# Dot_matrix_V1_1.net
KiCad netlist of a schematic drawn in Altium Designer
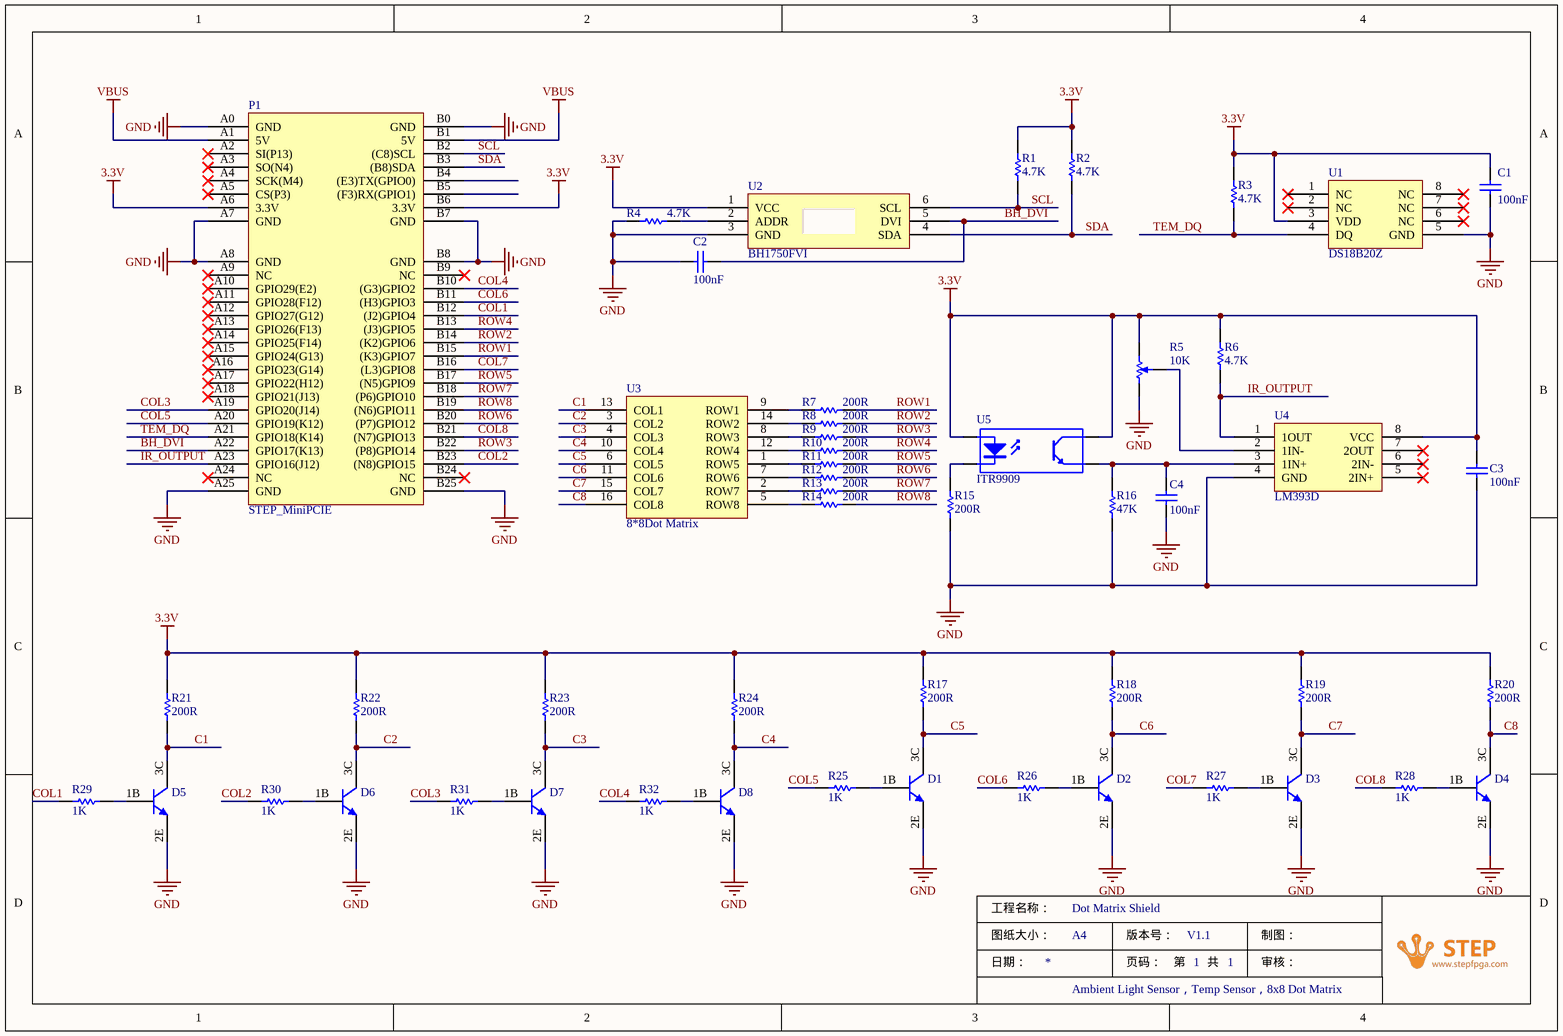
[diagram p0: Dot_matrix_V1.1.SchDoc]

(export (version "E")
  (design (tool "Eeschema 10.0.6"))
  (components
    (comp (ref "C1")
      (value "100nF")
      (footprint "CAP0603")
      (description "Capacitor")
      (libsource (lib "Ze_Zhang") (part "Cap"))
    )
    (comp (ref "C2")
      (value "100nF")
      (footprint "CAP0603")
      (description "Capacitor")
      (libsource (lib "Ze_Zhang") (part "Cap"))
    )
    (comp (ref "C3")
      (value "100nF")
      (footprint "CAP0603")
      (description "Capacitor")
      (libsource (lib "Ze_Zhang") (part "Cap"))
    )
    (comp (ref "C4")
      (value "100nF")
      (footprint "CAP0603")
      (description "Capacitor")
      (libsource (lib "Ze_Zhang") (part "Cap"))
    )
    (comp (ref "D1")
      (value "s9013")
      (footprint "SOT-23 s9013")
      (description "NPN三极管")
      (libsource (lib "Ze_Zhang") (part "s9013"))
    )
    (comp (ref "D2")
      (value "s9013")
      (footprint "SOT-23 s9013")
      (description "NPN三极管")
      (libsource (lib "Ze_Zhang") (part "s9013"))
    )
    (comp (ref "D3")
      (value "s9013")
      (footprint "SOT-23 s9013")
      (description "NPN三极管")
      (libsource (lib "Ze_Zhang") (part "s9013"))
    )
    (comp (ref "D4")
      (value "s9013")
      (footprint "SOT-23 s9013")
      (description "NPN三极管")
      (libsource (lib "Ze_Zhang") (part "s9013"))
    )
    (comp (ref "D5")
      (value "s9013")
      (footprint "SOT-23 s9013")
      (description "NPN三极管")
      (libsource (lib "Ze_Zhang") (part "s9013"))
    )
    (comp (ref "D6")
      (value "s9013")
      (footprint "SOT-23 s9013")
      (description "NPN三极管")
      (libsource (lib "Ze_Zhang") (part "s9013"))
    )
    (comp (ref "D7")
      (value "s9013")
      (footprint "SOT-23 s9013")
      (description "NPN三极管")
      (libsource (lib "Ze_Zhang") (part "s9013"))
    )
    (comp (ref "D8")
      (value "s9013")
      (footprint "SOT-23 s9013")
      (description "NPN三极管")
      (libsource (lib "Ze_Zhang") (part "s9013"))
    )
    (comp (ref "P1")
      (value "STEP_MiniPCIE")
      (footprint "STEP_miniPCI-E")
      (description "8mm MiniPCIE interface")
      (libsource (lib "Ze_Zhang") (part "STEP_MiniPCIE"))
    )
    (comp (ref "R1") (value "4.7K") (footprint "RES0603") (libsource (lib "Ze_Zhang") (part "Res")))
    (comp (ref "R2") (value "4.7K") (footprint "RES0603") (libsource (lib "Ze_Zhang") (part "Res")))
    (comp (ref "R3") (value "4.7K") (footprint "RES0603") (libsource (lib "Ze_Zhang") (part "Res")))
    (comp (ref "R4") (value "4.7K") (footprint "RES0603") (libsource (lib "Ze_Zhang") (part "Res")))
    (comp (ref "R5")
      (value "10K")
      (footprint "POT3MM")
      (description "可调电阻3mm*3mm")
      (fields (field (name "PARTNUMBER") "EXM3GSX50B14") (field (name "MANUFACTURER") "Panasonic"))
      (libsource (lib "Ze_Zhang") (part "Square Trimming Potentiometer"))
    )
    (comp (ref "R6") (value "4.7K") (footprint "RES0603") (libsource (lib "Ze_Zhang") (part "Res")))
    (comp (ref "R7") (value "200R") (footprint "RES0603") (libsource (lib "Ze_Zhang") (part "Res")))
    (comp (ref "R8") (value "200R") (footprint "RES0603") (libsource (lib "Ze_Zhang") (part "Res")))
    (comp (ref "R9") (value "200R") (footprint "RES0603") (libsource (lib "Ze_Zhang") (part "Res")))
    (comp (ref "R10") (value "200R") (footprint "RES0603") (libsource (lib "Ze_Zhang") (part "Res")))
    (comp (ref "R11") (value "200R") (footprint "RES0603") (libsource (lib "Ze_Zhang") (part "Res")))
    (comp (ref "R12") (value "200R") (footprint "RES0603") (libsource (lib "Ze_Zhang") (part "Res")))
    (comp (ref "R13") (value "200R") (footprint "RES0603") (libsource (lib "Ze_Zhang") (part "Res")))
    (comp (ref "R14") (value "200R") (footprint "RES0603") (libsource (lib "Ze_Zhang") (part "Res")))
    (comp (ref "R15") (value "200R") (footprint "RES0603") (libsource (lib "Ze_Zhang") (part "Res")))
    (comp (ref "R16") (value "47K") (footprint "RES0603") (libsource (lib "Ze_Zhang") (part "Res")))
    (comp (ref "R17") (value "200R") (footprint "RES0603") (libsource (lib "Ze_Zhang") (part "Res")))
    (comp (ref "R18") (value "200R") (footprint "RES0603") (libsource (lib "Ze_Zhang") (part "Res")))
    (comp (ref "R19") (value "200R") (footprint "RES0603") (libsource (lib "Ze_Zhang") (part "Res")))
    (comp (ref "R20") (value "200R") (footprint "RES0603") (libsource (lib "Ze_Zhang") (part "Res")))
    (comp (ref "R21") (value "200R") (footprint "RES0603") (libsource (lib "Ze_Zhang") (part "Res")))
    (comp (ref "R22") (value "200R") (footprint "RES0603") (libsource (lib "Ze_Zhang") (part "Res")))
    (comp (ref "R23") (value "200R") (footprint "RES0603") (libsource (lib "Ze_Zhang") (part "Res")))
    (comp (ref "R24") (value "200R") (footprint "RES0603") (libsource (lib "Ze_Zhang") (part "Res")))
    (comp (ref "R25") (value "1K") (footprint "RES0603") (libsource (lib "Ze_Zhang") (part "Res")))
    (comp (ref "R26") (value "1K") (footprint "RES0603") (libsource (lib "Ze_Zhang") (part "Res")))
    (comp (ref "R27") (value "1K") (footprint "RES0603") (libsource (lib "Ze_Zhang") (part "Res")))
    (comp (ref "R28") (value "1K") (footprint "RES0603") (libsource (lib "Ze_Zhang") (part "Res")))
    (comp (ref "R29") (value "1K") (footprint "RES0603") (libsource (lib "Ze_Zhang") (part "Res")))
    (comp (ref "R30") (value "1K") (footprint "RES0603") (libsource (lib "Ze_Zhang") (part "Res")))
    (comp (ref "R31") (value "1K") (footprint "RES0603") (libsource (lib "Ze_Zhang") (part "Res")))
    (comp (ref "R32") (value "1K") (footprint "RES0603") (libsource (lib "Ze_Zhang") (part "Res")))
    (comp (ref "U1")
      (value "DS18B20Z")
      (footprint "SOP8")
      (description "温度传感器DS18B20,单总线，SOP8封装")
      (fields (field (name "MANUFACTURER") "Dallas"))
      (libsource (lib "Ze_Zhang") (part "DS18B20Z"))
    )
    (comp (ref "U2")
      (value "BH1750FVI")
      (footprint "WSOF6I")
      (description "I2C接口环境光传感器")
      (fields (field (name "MANUFACTURER") "RHOM"))
      (libsource (lib "Ze_Zhang") (part "BH1750FVI"))
    )
    (comp (ref "U3")
      (value "8*8Dot Matrix")
      (footprint "8*8Dot Matrix")
      (description "8*8LED点阵，尺寸为32mm*32mm , 共阴")
      (fields (field (name "PARTNUMBER") "1088AS"))
      (libsource (lib "Ze_Zhang") (part "8*8Dot Matrix"))
    )
    (comp (ref "U4")
      (value "LM393D")
      (footprint "SOP8")
      (description "双路电压比较器")
      (fields (field (name "MANUFACTURER") "Texas Instruments"))
      (libsource (lib "Ze_Zhang") (part "LM393D"))
    )
    (comp (ref "U5")
      (value "ITR9909")
      (footprint "ITR9909")
      (description "红外对管，4pins")
      (fields (field (name "MANUFACTURER") "EVERLIGHT  ELECTRONICS"))
      (libsource (lib "Ze_Zhang") (part "ITR9909"))
    )
  )
  (nets
    (net (code "1") (name "/BH_DVI") (class "Default")
      (node (ref "C2") (pin "1") (pinfunction "1_1") (pintype "passive"))
      (node (ref "P1") (pin "A22") (pinfunction "GPIO17(K13)_A22") (pintype "passive"))
      (node (ref "U2") (pin "5") (pinfunction "DVI_5") (pintype "passive"))
    )
    (net (code "2") (name "/C1") (class "Default")
      (node (ref "D5") (pin "3C") (pinfunction "3C_3C") (pintype "passive"))
      (node (ref "R21") (pin "1") (pinfunction "1_1") (pintype "passive"))
      (node (ref "U3") (pin "13") (pinfunction "COL1_13") (pintype "passive"))
    )
    (net (code "3") (name "/C2") (class "Default")
      (node (ref "D6") (pin "3C") (pinfunction "3C_3C") (pintype "passive"))
      (node (ref "R22") (pin "1") (pinfunction "1_1") (pintype "passive"))
      (node (ref "U3") (pin "3") (pinfunction "COL2_3") (pintype "passive"))
    )
    (net (code "4") (name "/C3") (class "Default")
      (node (ref "D7") (pin "3C") (pinfunction "3C_3C") (pintype "passive"))
      (node (ref "R23") (pin "1") (pinfunction "1_1") (pintype "passive"))
      (node (ref "U3") (pin "4") (pinfunction "COL3_4") (pintype "passive"))
    )
    (net (code "5") (name "/C4") (class "Default")
      (node (ref "D8") (pin "3C") (pinfunction "3C_3C") (pintype "passive"))
      (node (ref "R24") (pin "1") (pinfunction "1_1") (pintype "passive"))
      (node (ref "U3") (pin "10") (pinfunction "COL4_10") (pintype "passive"))
    )
    (net (code "6") (name "/C5") (class "Default")
      (node (ref "D1") (pin "3C") (pinfunction "3C_3C") (pintype "passive"))
      (node (ref "R17") (pin "1") (pinfunction "1_1") (pintype "passive"))
      (node (ref "U3") (pin "6") (pinfunction "COL5_6") (pintype "passive"))
    )
    (net (code "7") (name "/C6") (class "Default")
      (node (ref "D2") (pin "3C") (pinfunction "3C_3C") (pintype "passive"))
      (node (ref "R18") (pin "1") (pinfunction "1_1") (pintype "passive"))
      (node (ref "U3") (pin "11") (pinfunction "COL6_11") (pintype "passive"))
    )
    (net (code "8") (name "/C7") (class "Default")
      (node (ref "D3") (pin "3C") (pinfunction "3C_3C") (pintype "passive"))
      (node (ref "R19") (pin "1") (pinfunction "1_1") (pintype "passive"))
      (node (ref "U3") (pin "15") (pinfunction "COL7_15") (pintype "passive"))
    )
    (net (code "9") (name "/C8") (class "Default")
      (node (ref "D4") (pin "3C") (pinfunction "3C_3C") (pintype "passive"))
      (node (ref "R20") (pin "1") (pinfunction "1_1") (pintype "passive"))
      (node (ref "U3") (pin "16") (pinfunction "COL8_16") (pintype "passive"))
    )
    (net (code "10") (name "/COL1") (class "Default")
      (node (ref "P1") (pin "B12") (pinfunction "(J2)GPIO4_B12") (pintype "passive"))
      (node (ref "R29") (pin "1") (pinfunction "1_1") (pintype "passive"))
    )
    (net (code "11") (name "/COL2") (class "Default")
      (node (ref "P1") (pin "B23") (pinfunction "(N8)GPIO15_B23") (pintype "passive"))
      (node (ref "R30") (pin "1") (pinfunction "1_1") (pintype "passive"))
    )
    (net (code "12") (name "/COL3") (class "Default")
      (node (ref "P1") (pin "A19") (pinfunction "GPIO20(J14)_A19") (pintype "passive"))
      (node (ref "R31") (pin "1") (pinfunction "1_1") (pintype "passive"))
    )
    (net (code "13") (name "/COL4") (class "Default")
      (node (ref "P1") (pin "B10") (pinfunction "(G3)GPIO2_B10") (pintype "passive"))
      (node (ref "R32") (pin "1") (pinfunction "1_1") (pintype "passive"))
    )
    (net (code "14") (name "/COL5") (class "Default")
      (node (ref "P1") (pin "A20") (pinfunction "GPIO19(K12)_A20") (pintype "passive"))
      (node (ref "R25") (pin "1") (pinfunction "1_1") (pintype "passive"))
    )
    (net (code "15") (name "/COL6") (class "Default")
      (node (ref "P1") (pin "B11") (pinfunction "(H3)GPIO3_B11") (pintype "passive"))
      (node (ref "R26") (pin "1") (pinfunction "1_1") (pintype "passive"))
    )
    (net (code "16") (name "/COL7") (class "Default")
      (node (ref "P1") (pin "B16") (pinfunction "(L3)GPIO8_B16") (pintype "passive"))
      (node (ref "R27") (pin "1") (pinfunction "1_1") (pintype "passive"))
    )
    (net (code "17") (name "/COL8") (class "Default")
      (node (ref "P1") (pin "B21") (pinfunction "(N7)GPIO13_B21") (pintype "passive"))
      (node (ref "R28") (pin "1") (pinfunction "1_1") (pintype "passive"))
    )
    (net (code "18") (name "/IR_OUTPUT") (class "Default")
      (node (ref "P1") (pin "A23") (pinfunction "GPIO16(J12)_A23") (pintype "passive"))
      (node (ref "R6") (pin "1") (pinfunction "1_1") (pintype "passive"))
      (node (ref "U4") (pin "1") (pinfunction "1OUT_1") (pintype "passive"))
    )
    (net (code "19") (name "/ROW1") (class "Default")
      (node (ref "P1") (pin "B15") (pinfunction "(K3)GPIO7_B15") (pintype "passive"))
      (node (ref "R7") (pin "2") (pinfunction "2_2") (pintype "passive"))
    )
    (net (code "20") (name "/ROW2") (class "Default")
      (node (ref "P1") (pin "B14") (pinfunction "(K2)GPIO6_B14") (pintype "passive"))
      (node (ref "R8") (pin "2") (pinfunction "2_2") (pintype "passive"))
    )
    (net (code "21") (name "/ROW3") (class "Default")
      (node (ref "P1") (pin "B22") (pinfunction "(P8)GPIO14_B22") (pintype "passive"))
      (node (ref "R9") (pin "2") (pinfunction "2_2") (pintype "passive"))
    )
    (net (code "22") (name "/ROW4") (class "Default")
      (node (ref "P1") (pin "B13") (pinfunction "(J3)GPIO5_B13") (pintype "passive"))
      (node (ref "R10") (pin "2") (pinfunction "2_2") (pintype "passive"))
    )
    (net (code "23") (name "/ROW5") (class "Default")
      (node (ref "P1") (pin "B17") (pinfunction "(N5)GPIO9_B17") (pintype "passive"))
      (node (ref "R11") (pin "2") (pinfunction "2_2") (pintype "passive"))
    )
    (net (code "24") (name "/ROW6") (class "Default")
      (node (ref "P1") (pin "B20") (pinfunction "(P7)GPIO12_B20") (pintype "passive"))
      (node (ref "R12") (pin "2") (pinfunction "2_2") (pintype "passive"))
    )
    (net (code "25") (name "/ROW7") (class "Default")
      (node (ref "P1") (pin "B18") (pinfunction "(P6)GPIO10_B18") (pintype "passive"))
      (node (ref "R13") (pin "2") (pinfunction "2_2") (pintype "passive"))
    )
    (net (code "26") (name "/ROW8") (class "Default")
      (node (ref "P1") (pin "B19") (pinfunction "(N6)GPIO11_B19") (pintype "passive"))
      (node (ref "R14") (pin "2") (pinfunction "2_2") (pintype "passive"))
    )
    (net (code "27") (name "/SCL") (class "Default")
      (node (ref "P1") (pin "B2") (pinfunction "(C8)SCL_B2") (pintype "passive"))
      (node (ref "R1") (pin "1") (pinfunction "1_1") (pintype "passive"))
      (node (ref "U2") (pin "6") (pinfunction "SCL_6") (pintype "passive"))
    )
    (net (code "28") (name "/SDA") (class "Default")
      (node (ref "P1") (pin "B3") (pinfunction "(B8)SDA_B3") (pintype "passive"))
      (node (ref "R2") (pin "1") (pinfunction "1_1") (pintype "passive"))
      (node (ref "U2") (pin "4") (pinfunction "SDA_4") (pintype "passive"))
    )
    (net (code "29") (name "/TEM_DQ") (class "Default")
      (node (ref "P1") (pin "A21") (pinfunction "GPIO18(K14)_A21") (pintype "passive"))
      (node (ref "R3") (pin "1") (pinfunction "1_1") (pintype "passive"))
      (node (ref "U1") (pin "4") (pinfunction "DQ_4") (pintype "passive"))
    )
    (net (code "30") (name "3.3V") (class "Default")
      (node (ref "C1") (pin "2") (pinfunction "2_2") (pintype "passive"))
      (node (ref "C3") (pin "2") (pinfunction "2_2") (pintype "passive"))
      (node (ref "P1") (pin "A6") (pinfunction "3.3V_A6") (pintype "passive"))
      (node (ref "P1") (pin "B6") (pinfunction "3.3V_B6") (pintype "passive"))
      (node (ref "R1") (pin "2") (pinfunction "2_2") (pintype "passive"))
      (node (ref "R17") (pin "2") (pinfunction "2_2") (pintype "passive"))
      (node (ref "R18") (pin "2") (pinfunction "2_2") (pintype "passive"))
      (node (ref "R19") (pin "2") (pinfunction "2_2") (pintype "passive"))
      (node (ref "R2") (pin "2") (pinfunction "2_2") (pintype "passive"))
      (node (ref "R20") (pin "2") (pinfunction "2_2") (pintype "passive"))
      (node (ref "R21") (pin "2") (pinfunction "2_2") (pintype "passive"))
      (node (ref "R22") (pin "2") (pinfunction "2_2") (pintype "passive"))
      (node (ref "R23") (pin "2") (pinfunction "2_2") (pintype "passive"))
      (node (ref "R24") (pin "2") (pinfunction "2_2") (pintype "passive"))
      (node (ref "R3") (pin "2") (pinfunction "2_2") (pintype "passive"))
      (node (ref "R5") (pin "CW") (pinfunction "+_CW") (pintype "passive"))
      (node (ref "R6") (pin "2") (pinfunction "2_2") (pintype "passive"))
      (node (ref "U1") (pin "3") (pinfunction "VDD_3") (pintype "passive"))
      (node (ref "U2") (pin "1") (pinfunction "VCC_1") (pintype "passive"))
      (node (ref "U4") (pin "8") (pinfunction "VCC_8") (pintype "passive"))
      (node (ref "U5") (pin "2") (pinfunction "2_2") (pintype "passive"))
      (node (ref "U5") (pin "4") (pinfunction "4_4") (pintype "passive"))
    )
    (net (code "31") (name "GND") (class "Default")
      (node (ref "C1") (pin "1") (pinfunction "1_1") (pintype "passive"))
      (node (ref "C2") (pin "2") (pinfunction "2_2") (pintype "passive"))
      (node (ref "C3") (pin "1") (pinfunction "1_1") (pintype "passive"))
      (node (ref "C4") (pin "1") (pinfunction "1_1") (pintype "passive"))
      (node (ref "D1") (pin "2E") (pinfunction "2E_2E") (pintype "passive"))
      (node (ref "D2") (pin "2E") (pinfunction "2E_2E") (pintype "passive"))
      (node (ref "D3") (pin "2E") (pinfunction "2E_2E") (pintype "passive"))
      (node (ref "D4") (pin "2E") (pinfunction "2E_2E") (pintype "passive"))
      (node (ref "D5") (pin "2E") (pinfunction "2E_2E") (pintype "passive"))
      (node (ref "D6") (pin "2E") (pinfunction "2E_2E") (pintype "passive"))
      (node (ref "D7") (pin "2E") (pinfunction "2E_2E") (pintype "passive"))
      (node (ref "D8") (pin "2E") (pinfunction "2E_2E") (pintype "passive"))
      (node (ref "P1") (pin "A0") (pinfunction "GND_A0") (pintype "passive"))
      (node (ref "P1") (pin "A25") (pinfunction "GND_A25") (pintype "passive"))
      (node (ref "P1") (pin "A7") (pinfunction "GND_A7") (pintype "passive"))
      (node (ref "P1") (pin "A8") (pinfunction "GND_A8") (pintype "passive"))
      (node (ref "P1") (pin "B0") (pinfunction "GND_B0") (pintype "passive"))
      (node (ref "P1") (pin "B25") (pinfunction "GND_B25") (pintype "passive"))
      (node (ref "P1") (pin "B7") (pinfunction "GND_B7") (pintype "passive"))
      (node (ref "P1") (pin "B8") (pinfunction "GND_B8") (pintype "passive"))
      (node (ref "R15") (pin "1") (pinfunction "1_1") (pintype "passive"))
      (node (ref "R16") (pin "1") (pinfunction "1_1") (pintype "passive"))
      (node (ref "R4") (pin "1") (pinfunction "1_1") (pintype "passive"))
      (node (ref "R5") (pin "CCW") (pinfunction "-_CCW") (pintype "passive"))
      (node (ref "U1") (pin "5") (pinfunction "GND_5") (pintype "passive"))
      (node (ref "U2") (pin "3") (pinfunction "GND_3") (pintype "passive"))
      (node (ref "U4") (pin "4") (pinfunction "GND_4") (pintype "passive"))
    )
    (net (code "32") (name "Net-(D1-Pad1B)") (class "Default")
      (node (ref "D1") (pin "1B") (pinfunction "1B_1B") (pintype "passive"))
      (node (ref "R25") (pin "2") (pinfunction "2_2") (pintype "passive"))
    )
    (net (code "33") (name "Net-(D2-Pad1B)") (class "Default")
      (node (ref "D2") (pin "1B") (pinfunction "1B_1B") (pintype "passive"))
      (node (ref "R26") (pin "2") (pinfunction "2_2") (pintype "passive"))
    )
    (net (code "34") (name "Net-(D3-Pad1B)") (class "Default")
      (node (ref "D3") (pin "1B") (pinfunction "1B_1B") (pintype "passive"))
      (node (ref "R27") (pin "2") (pinfunction "2_2") (pintype "passive"))
    )
    (net (code "35") (name "Net-(D4-Pad1B)") (class "Default")
      (node (ref "D4") (pin "1B") (pinfunction "1B_1B") (pintype "passive"))
      (node (ref "R28") (pin "2") (pinfunction "2_2") (pintype "passive"))
    )
    (net (code "36") (name "Net-(D5-Pad1B)") (class "Default")
      (node (ref "D5") (pin "1B") (pinfunction "1B_1B") (pintype "passive"))
      (node (ref "R29") (pin "2") (pinfunction "2_2") (pintype "passive"))
    )
    (net (code "37") (name "Net-(D6-Pad1B)") (class "Default")
      (node (ref "D6") (pin "1B") (pinfunction "1B_1B") (pintype "passive"))
      (node (ref "R30") (pin "2") (pinfunction "2_2") (pintype "passive"))
    )
    (net (code "38") (name "Net-(D7-Pad1B)") (class "Default")
      (node (ref "D7") (pin "1B") (pinfunction "1B_1B") (pintype "passive"))
      (node (ref "R31") (pin "2") (pinfunction "2_2") (pintype "passive"))
    )
    (net (code "39") (name "Net-(D8-Pad1B)") (class "Default")
      (node (ref "D8") (pin "1B") (pinfunction "1B_1B") (pintype "passive"))
      (node (ref "R32") (pin "2") (pinfunction "2_2") (pintype "passive"))
    )
    (net (code "40") (name "Net-(R15-Pad2)") (class "Default")
      (node (ref "R15") (pin "2") (pinfunction "2_2") (pintype "passive"))
      (node (ref "U5") (pin "1") (pinfunction "1_1") (pintype "passive"))
    )
    (net (code "41") (name "Net-(U2-ADDR)") (class "Default")
      (node (ref "R4") (pin "2") (pinfunction "2_2") (pintype "passive"))
      (node (ref "U2") (pin "2") (pinfunction "ADDR_2") (pintype "passive"))
    )
    (net (code "42") (name "Net-(U3-ROW1)") (class "Default")
      (node (ref "R7") (pin "1") (pinfunction "1_1") (pintype "passive"))
      (node (ref "U3") (pin "9") (pinfunction "ROW1_9") (pintype "passive"))
    )
    (net (code "43") (name "Net-(U3-ROW2)") (class "Default")
      (node (ref "R8") (pin "1") (pinfunction "1_1") (pintype "passive"))
      (node (ref "U3") (pin "14") (pinfunction "ROW2_14") (pintype "passive"))
    )
    (net (code "44") (name "Net-(U3-ROW3)") (class "Default")
      (node (ref "R9") (pin "1") (pinfunction "1_1") (pintype "passive"))
      (node (ref "U3") (pin "8") (pinfunction "ROW3_8") (pintype "passive"))
    )
    (net (code "45") (name "Net-(U3-ROW4)") (class "Default")
      (node (ref "R10") (pin "1") (pinfunction "1_1") (pintype "passive"))
      (node (ref "U3") (pin "12") (pinfunction "ROW4_12") (pintype "passive"))
    )
    (net (code "46") (name "Net-(U3-ROW5)") (class "Default")
      (node (ref "R11") (pin "1") (pinfunction "1_1") (pintype "passive"))
      (node (ref "U3") (pin "1") (pinfunction "ROW5_1") (pintype "passive"))
    )
    (net (code "47") (name "Net-(U3-ROW6)") (class "Default")
      (node (ref "R12") (pin "1") (pinfunction "1_1") (pintype "passive"))
      (node (ref "U3") (pin "7") (pinfunction "ROW6_7") (pintype "passive"))
    )
    (net (code "48") (name "Net-(U3-ROW7)") (class "Default")
      (node (ref "R13") (pin "1") (pinfunction "1_1") (pintype "passive"))
      (node (ref "U3") (pin "2") (pinfunction "ROW7_2") (pintype "passive"))
    )
    (net (code "49") (name "Net-(U3-ROW8)") (class "Default")
      (node (ref "R14") (pin "1") (pinfunction "1_1") (pintype "passive"))
      (node (ref "U3") (pin "5") (pinfunction "ROW8_5") (pintype "passive"))
    )
    (net (code "50") (name "Net-(U4-1IN+)") (class "Default")
      (node (ref "C4") (pin "2") (pinfunction "2_2") (pintype "passive"))
      (node (ref "R16") (pin "2") (pinfunction "2_2") (pintype "passive"))
      (node (ref "U4") (pin "3") (pinfunction "1IN+_3") (pintype "passive"))
      (node (ref "U5") (pin "3") (pinfunction "3_3") (pintype "passive"))
    )
    (net (code "51") (name "Net-(U4-1IN-)") (class "Default")
      (node (ref "R5") (pin "W") (pinfunction "W_W") (pintype "passive"))
      (node (ref "U4") (pin "2") (pinfunction "1IN-_2") (pintype "passive"))
    )
    (net (code "52") (name "VBUS") (class "Default")
      (node (ref "P1") (pin "A1") (pinfunction "5V_A1") (pintype "passive"))
      (node (ref "P1") (pin "B1") (pinfunction "5V_B1") (pintype "passive"))
    )
    (net (code "53") (name "unconnected-(P1-(E3)TX(GPIO0)-PadB4)") (class "Default")
      (node (ref "P1") (pin "B4") (pinfunction "(E3)TX(GPIO0)_B4") (pintype "passive"))
    )
    (net (code "54") (name "unconnected-(P1-(F3)RX(GPIO1)-PadB5)") (class "Default")
      (node (ref "P1") (pin "B5") (pinfunction "(F3)RX(GPIO1)_B5") (pintype "passive"))
    )
    (net (code "55") (name "unconnected-(P1-CS(P3)-PadA5)") (class "Default")
      (node (ref "P1") (pin "A5") (pinfunction "CS(P3)_A5") (pintype "passive+no_connect"))
    )
    (net (code "56") (name "unconnected-(P1-GPIO21(J13)-PadA18)") (class "Default")
      (node (ref "P1") (pin "A18") (pinfunction "GPIO21(J13)_A18") (pintype "passive+no_connect"))
    )
    (net (code "57") (name "unconnected-(P1-GPIO22(H12)-PadA17)") (class "Default")
      (node (ref "P1") (pin "A17") (pinfunction "GPIO22(H12)_A17") (pintype "passive+no_connect"))
    )
    (net (code "58") (name "unconnected-(P1-GPIO23(G14)-PadA16)") (class "Default")
      (node (ref "P1") (pin "A16") (pinfunction "GPIO23(G14)_A16") (pintype "passive+no_connect"))
    )
    (net (code "59") (name "unconnected-(P1-GPIO24(G13)-PadA15)") (class "Default")
      (node (ref "P1") (pin "A15") (pinfunction "GPIO24(G13)_A15") (pintype "passive+no_connect"))
    )
    (net (code "60") (name "unconnected-(P1-GPIO25(F14)-PadA14)") (class "Default")
      (node (ref "P1") (pin "A14") (pinfunction "GPIO25(F14)_A14") (pintype "passive+no_connect"))
    )
    (net (code "61") (name "unconnected-(P1-GPIO26(F13)-PadA13)") (class "Default")
      (node (ref "P1") (pin "A13") (pinfunction "GPIO26(F13)_A13") (pintype "passive+no_connect"))
    )
    (net (code "62") (name "unconnected-(P1-GPIO27(G12)-PadA12)") (class "Default")
      (node (ref "P1") (pin "A12") (pinfunction "GPIO27(G12)_A12") (pintype "passive+no_connect"))
    )
    (net (code "63") (name "unconnected-(P1-GPIO28(F12)-PadA11)") (class "Default")
      (node (ref "P1") (pin "A11") (pinfunction "GPIO28(F12)_A11") (pintype "passive+no_connect"))
    )
    (net (code "64") (name "unconnected-(P1-GPIO29(E2)-PadA10)") (class "Default")
      (node (ref "P1") (pin "A10") (pinfunction "GPIO29(E2)_A10") (pintype "passive+no_connect"))
    )
    (net (code "65") (name "unconnected-(P1-NC-PadA9)") (class "Default")
      (node (ref "P1") (pin "A9") (pinfunction "NC_A9") (pintype "passive+no_connect"))
    )
    (net (code "66") (name "unconnected-(P1-NC-PadA24)") (class "Default")
      (node (ref "P1") (pin "A24") (pinfunction "NC_A24") (pintype "passive+no_connect"))
    )
    (net (code "67") (name "unconnected-(P1-NC-PadB9)") (class "Default")
      (node (ref "P1") (pin "B9") (pinfunction "NC_B9") (pintype "passive+no_connect"))
    )
    (net (code "68") (name "unconnected-(P1-NC-PadB24)") (class "Default")
      (node (ref "P1") (pin "B24") (pinfunction "NC_B24") (pintype "passive+no_connect"))
    )
    (net (code "69") (name "unconnected-(P1-SCK(M4)-PadA4)") (class "Default")
      (node (ref "P1") (pin "A4") (pinfunction "SCK(M4)_A4") (pintype "passive+no_connect"))
    )
    (net (code "70") (name "unconnected-(P1-SI(P13)-PadA2)") (class "Default")
      (node (ref "P1") (pin "A2") (pinfunction "SI(P13)_A2") (pintype "passive+no_connect"))
    )
    (net (code "71") (name "unconnected-(P1-SO(N4)-PadA3)") (class "Default")
      (node (ref "P1") (pin "A3") (pinfunction "SO(N4)_A3") (pintype "passive+no_connect"))
    )
    (net (code "72") (name "unconnected-(U1-NC-Pad1)") (class "Default")
      (node (ref "U1") (pin "1") (pinfunction "NC_1") (pintype "passive+no_connect"))
    )
    (net (code "73") (name "unconnected-(U1-NC-Pad2)") (class "Default")
      (node (ref "U1") (pin "2") (pinfunction "NC_2") (pintype "passive+no_connect"))
    )
    (net (code "74") (name "unconnected-(U1-NC-Pad6)") (class "Default")
      (node (ref "U1") (pin "6") (pinfunction "NC_6") (pintype "passive+no_connect"))
    )
    (net (code "75") (name "unconnected-(U1-NC-Pad7)") (class "Default")
      (node (ref "U1") (pin "7") (pinfunction "NC_7") (pintype "passive+no_connect"))
    )
    (net (code "76") (name "unconnected-(U1-NC-Pad8)") (class "Default")
      (node (ref "U1") (pin "8") (pinfunction "NC_8") (pintype "passive+no_connect"))
    )
    (net (code "77") (name "unconnected-(U4-2IN+-Pad5)") (class "Default")
      (node (ref "U4") (pin "5") (pinfunction "2IN+_5") (pintype "passive+no_connect"))
    )
    (net (code "78") (name "unconnected-(U4-2IN--Pad6)") (class "Default")
      (node (ref "U4") (pin "6") (pinfunction "2IN-_6") (pintype "passive+no_connect"))
    )
    (net (code "79") (name "unconnected-(U4-2OUT-Pad7)") (class "Default")
      (node (ref "U4") (pin "7") (pinfunction "2OUT_7") (pintype "passive+no_connect"))
    )
  )
)
